# 07-General_I2C_Devices.net
KiCad netlist of a schematic drawn in Altium Designer
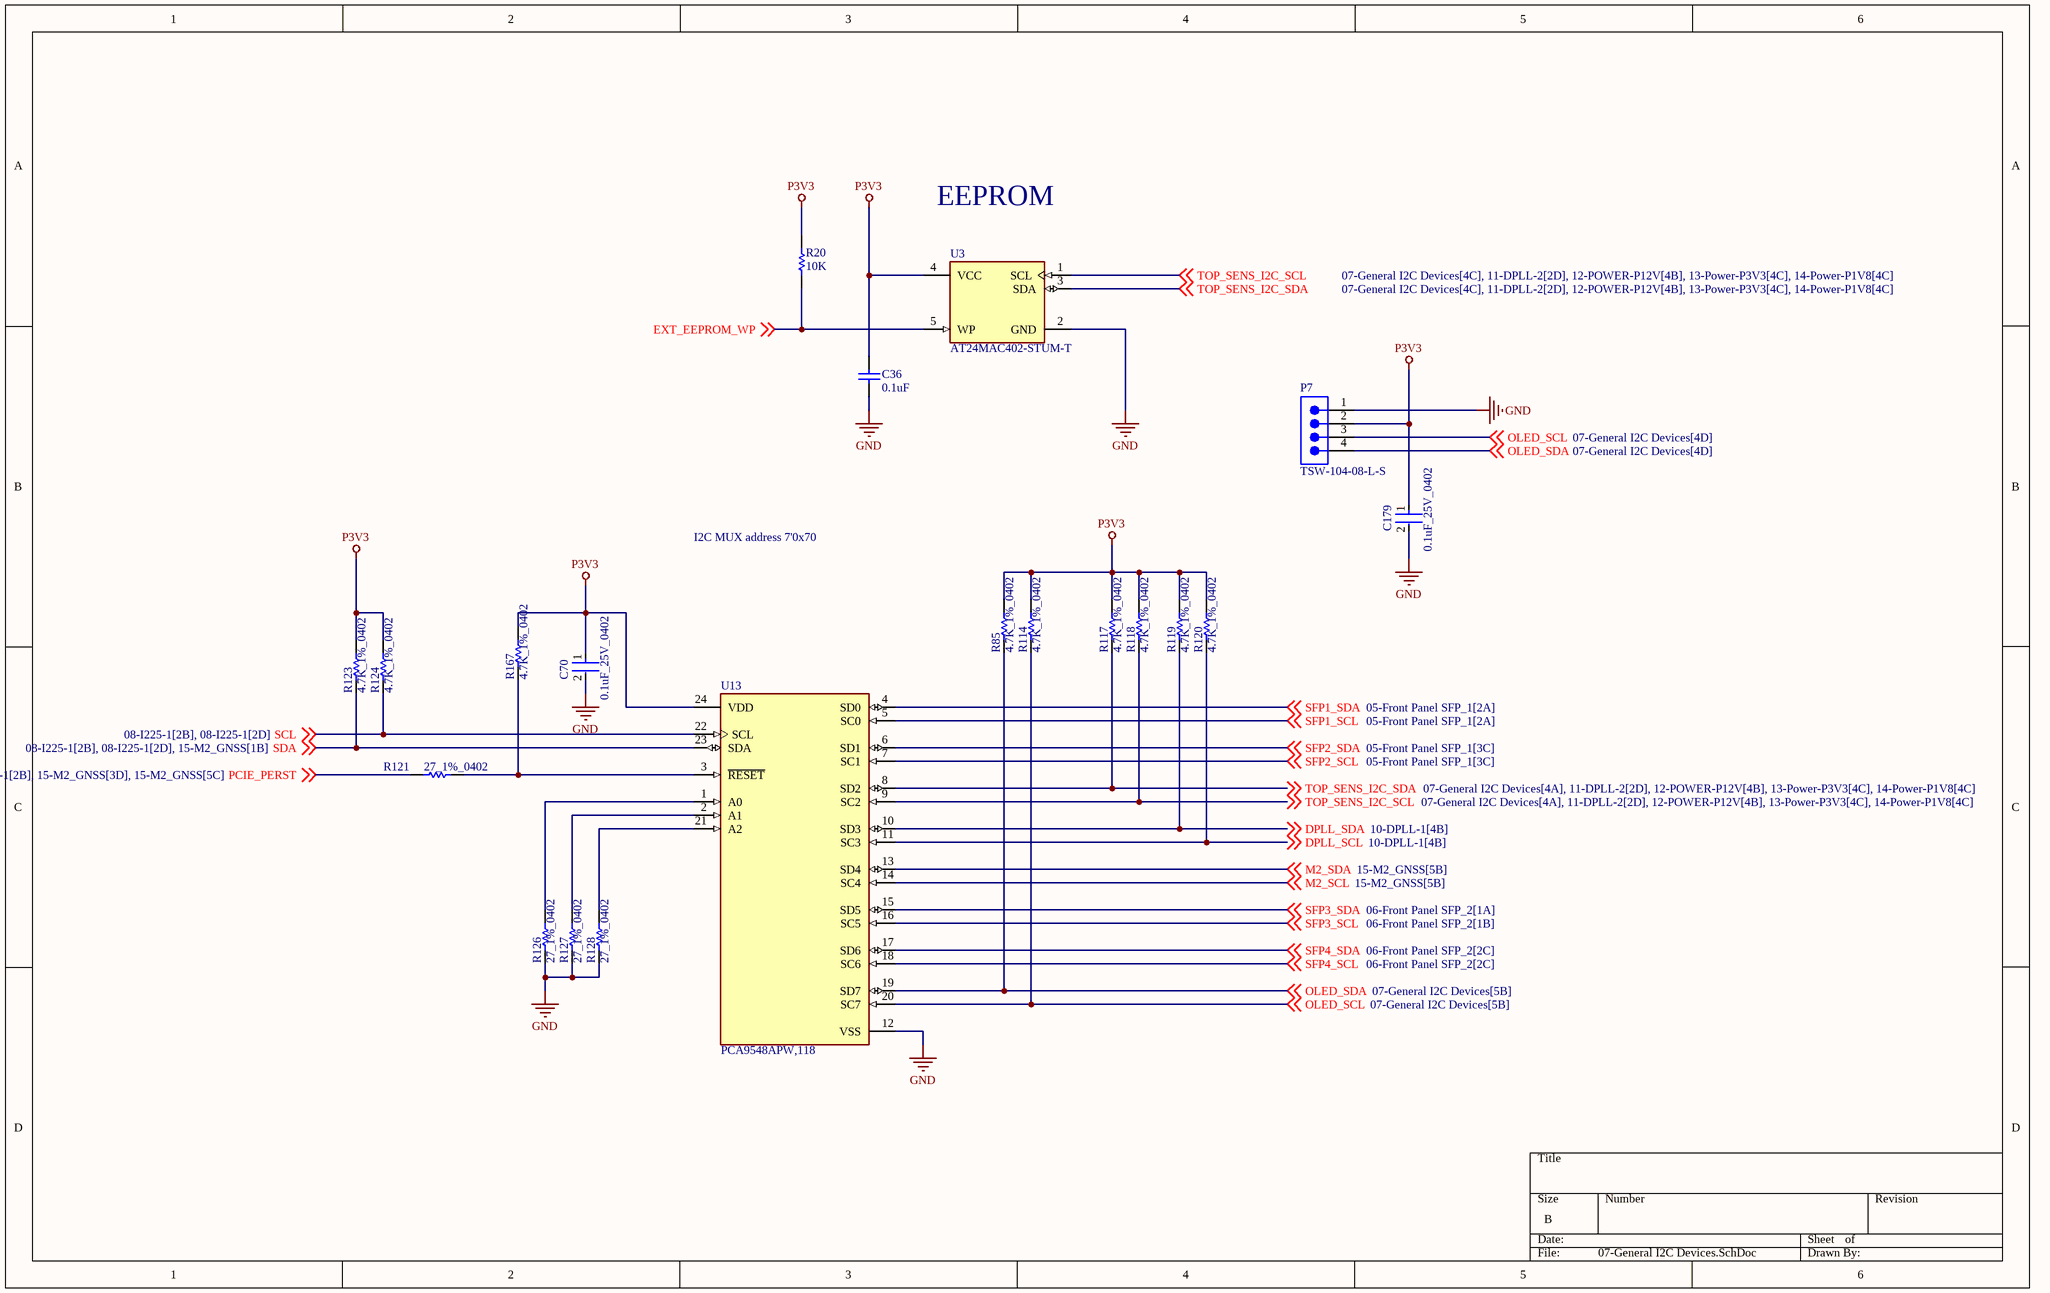
[diagram p0: 07-General I2C Devices.SchDoc]

(export (version "E")
  (design (tool "Eeschema 10.0.6"))
  (components
    (comp (ref "C36")
      (value "0.1uF")
      (footprint "CAPC1608X87X45ML20T05")
      (description "C0603X104K5RACAUTO")
      (fields (field (name "MANUFACTURER") "Kemet"))
      (libsource (lib "Altium Content Vault") (part "CAP"))
    )
    (comp (ref "C70")
      (value "0.1uF_25V_0402")
      (footprint "FP-0402-L_1_0_1-W_0_5_0_1-IPC_C")
      (description "General Purpose Ceramic Capacitor, 0402, 100nF, 10%, X7R, 15%, 25V")
      (fields (field (name "VOLTAGE") "25V") (field (name "TOLERANCE") "10%"))
      (libsource (lib "Altium Content Vault") (part "b4654b650e69147ec39a6b967a45e02"))
    )
    (comp (ref "C179")
      (value "0.1uF_25V_0402")
      (footprint "FP-0402-L_1_0_1-W_0_5_0_1-IPC_C")
      (description "General Purpose Ceramic Capacitor, 0402, 100nF, 10%, X7R, 15%, 25V")
      (fields (field (name "VOLTAGE") "25V") (field (name "TOLERANCE") "10%"))
      (libsource (lib "Altium Content Vault") (part "b4654b650e69147ec39a6b967a45e02"))
    )
    (comp (ref "P7")
      (value "TSW-104-08-L-S")
      (footprint "SMTC-TSW-104-08-X-S")
      (description "0.025\" SQ Post Header, Through-hole, Vertical, -55 to 125 degC, 2.54 mm Pitch, 4-Pin, Male, RoHS")
      (fields (field (name "MANUFACTURER") "Samtec"))
      (libsource (lib "Altium Content Vault") (part "SMTC-TSW-104-08-X-S"))
    )
    (comp (ref "R20")
      (value "10K")
      (footprint "RESC1608X55X30LL15T20")
      (fields (field (name "TOLERANCE") "±1%") (field (name "MANUFACTURER") "Stackpole-Electronics-Inc."))
      (libsource (lib "Altium Content Vault") (part "RES-2"))
    )
    (comp (ref "R85")
      (value "4.7K_1%_0402")
      (footprint "RESC1005X40X25NL10T10")
      (fields (field (name "MANUFACTURER") "Bourns") (field (name "PART NUMBER") "CR0402-FX-4701GLF"))
      (libsource (lib "Altium Content Vault") (part "RES"))
    )
    (comp (ref "R114")
      (value "4.7K_1%_0402")
      (footprint "RESC1005X40X25NL10T10")
      (fields (field (name "MANUFACTURER") "Bourns") (field (name "PART NUMBER") "CR0402-FX-4701GLF"))
      (libsource (lib "Altium Content Vault") (part "RES"))
    )
    (comp (ref "R117")
      (value "4.7K_1%_0402")
      (footprint "RESC1005X40X25NL10T10")
      (fields (field (name "MANUFACTURER") "Bourns") (field (name "PART NUMBER") "CR0402-FX-4701GLF"))
      (libsource (lib "Altium Content Vault") (part "RES"))
    )
    (comp (ref "R118")
      (value "4.7K_1%_0402")
      (footprint "RESC1005X40X25NL10T10")
      (fields (field (name "MANUFACTURER") "Bourns") (field (name "PART NUMBER") "CR0402-FX-4701GLF"))
      (libsource (lib "Altium Content Vault") (part "RES"))
    )
    (comp (ref "R119")
      (value "4.7K_1%_0402")
      (footprint "RESC1005X40X25NL10T10")
      (fields (field (name "MANUFACTURER") "Bourns") (field (name "PART NUMBER") "CR0402-FX-4701GLF"))
      (libsource (lib "Altium Content Vault") (part "RES"))
    )
    (comp (ref "R120")
      (value "4.7K_1%_0402")
      (footprint "RESC1005X40X25NL10T10")
      (fields (field (name "MANUFACTURER") "Bourns") (field (name "PART NUMBER") "CR0402-FX-4701GLF"))
      (libsource (lib "Altium Content Vault") (part "RES"))
    )
    (comp (ref "R121")
      (value "27_1%_0402")
      (footprint "RESC1005X40X25NL05T05")
      (fields (field (name "PART NUMBER") "CRCW040227R0FKED") (field (name "MANUFACTURER") "Vishay Dale"))
      (libsource (lib "Altium Content Vault") (part "RES"))
    )
    (comp (ref "R123")
      (value "4.7K_1%_0402")
      (footprint "RESC1005X40X25NL10T10")
      (fields (field (name "MANUFACTURER") "Bourns") (field (name "PART NUMBER") "CR0402-FX-4701GLF"))
      (libsource (lib "Altium Content Vault") (part "RES"))
    )
    (comp (ref "R124")
      (value "4.7K_1%_0402")
      (footprint "RESC1005X40X25NL10T10")
      (fields (field (name "MANUFACTURER") "Bourns") (field (name "PART NUMBER") "CR0402-FX-4701GLF"))
      (libsource (lib "Altium Content Vault") (part "RES"))
    )
    (comp (ref "R126")
      (value "27_1%_0402")
      (footprint "RESC1005X40X25NL05T05")
      (fields (field (name "PART NUMBER") "CRCW040227R0FKED") (field (name "MANUFACTURER") "Vishay Dale"))
      (libsource (lib "Altium Content Vault") (part "RES"))
    )
    (comp (ref "R127")
      (value "27_1%_0402")
      (footprint "RESC1005X40X25NL05T05")
      (fields (field (name "PART NUMBER") "CRCW040227R0FKED") (field (name "MANUFACTURER") "Vishay Dale"))
      (libsource (lib "Altium Content Vault") (part "RES"))
    )
    (comp (ref "R128")
      (value "27_1%_0402")
      (footprint "RESC1005X40X25NL05T05")
      (fields (field (name "PART NUMBER") "CRCW040227R0FKED") (field (name "MANUFACTURER") "Vishay Dale"))
      (libsource (lib "Altium Content Vault") (part "RES"))
    )
    (comp (ref "R167")
      (value "4.7K_1%_0402")
      (footprint "RESC1005X40X25NL10T10")
      (fields (field (name "MANUFACTURER") "Bourns") (field (name "PART NUMBER") "CR0402-FX-4701GLF"))
      (libsource (lib "Altium Content Vault") (part "RES"))
    )
    (comp (ref "U3")
      (value "AT24MAC402-STUM-T")
      (footprint "FP-5TS1-IPC_C")
      (description "IC EEPROM 2K I2C 1MHZ SOT23-5")
      (fields
        (field (name "MANUFACTURER") "Microchip")
        (field (name "OCTOPART") "https://octopart.com/at24mac402-stum-t-microchip-77758112")
      )
      (libsource (lib "Altium Content Vault") (part "93fe34f5f049140596bab6421a6454b"))
    )
    (comp (ref "U13")
      (value "PCA9548APW,118")
      (footprint "FP-SOT355-1-MFG")
      (description "IC INTERFACE SPECIALIZED 24TSSOP")
      (libsource (lib "Altium Content Vault") (part "3e168d29e2cae1e9eb34f21911d2ccb"))
    )
  )
  (nets
    (net (code "1") (name "DPLL_SCL") (class "Default")
      (node (ref "R120") (pin "1") (pinfunction "1_1") (pintype "passive"))
      (node (ref "U13") (pin "11") (pinfunction "SC3_11") (pintype "input"))
    )
    (net (code "2") (name "DPLL_SDA") (class "Default")
      (node (ref "R119") (pin "1") (pinfunction "1_1") (pintype "passive"))
      (node (ref "U13") (pin "10") (pinfunction "SD3_10") (pintype "bidirectional"))
    )
    (net (code "3") (name "EXT_EEPROM_WP") (class "Default")
      (node (ref "R20") (pin "1") (pinfunction "1_1") (pintype "passive"))
      (node (ref "U3") (pin "5") (pinfunction "WP_5") (pintype "input"))
    )
    (net (code "4") (name "GND") (class "Default")
      (node (ref "C179") (pin "2") (pinfunction "2_2") (pintype "passive"))
      (node (ref "C36") (pin "1") (pinfunction "1_1") (pintype "passive"))
      (node (ref "C70") (pin "2") (pinfunction "2_2") (pintype "passive"))
      (node (ref "P7") (pin "1") (pinfunction "1_1") (pintype "passive"))
      (node (ref "R126") (pin "1") (pinfunction "1_1") (pintype "passive"))
      (node (ref "R127") (pin "1") (pinfunction "1_1") (pintype "passive"))
      (node (ref "R128") (pin "1") (pinfunction "1_1") (pintype "passive"))
      (node (ref "U13") (pin "12") (pinfunction "VSS_12") (pintype "power_in"))
      (node (ref "U3") (pin "2") (pinfunction "GND_2") (pintype "power_in"))
    )
    (net (code "5") (name "M2_SCL") (class "Default")
      (node (ref "U13") (pin "14") (pinfunction "SC4_14") (pintype "input"))
    )
    (net (code "6") (name "M2_SDA") (class "Default")
      (node (ref "U13") (pin "13") (pinfunction "SD4_13") (pintype "bidirectional"))
    )
    (net (code "7") (name "Net-(U13-A0)") (class "Default")
      (node (ref "R126") (pin "2") (pinfunction "2_2") (pintype "passive"))
      (node (ref "U13") (pin "1") (pinfunction "A0_1") (pintype "input"))
    )
    (net (code "8") (name "Net-(U13-A1)") (class "Default")
      (node (ref "R127") (pin "2") (pinfunction "2_2") (pintype "passive"))
      (node (ref "U13") (pin "2") (pinfunction "A1_2") (pintype "input"))
    )
    (net (code "9") (name "Net-(U13-A2)") (class "Default")
      (node (ref "R128") (pin "2") (pinfunction "2_2") (pintype "passive"))
      (node (ref "U13") (pin "21") (pinfunction "A2_21") (pintype "input"))
    )
    (net (code "10") (name "Net-(U13-~{RESET})") (class "Default")
      (node (ref "R121") (pin "2") (pinfunction "2_2") (pintype "passive"))
      (node (ref "R167") (pin "1") (pinfunction "1_1") (pintype "passive"))
      (node (ref "U13") (pin "3") (pinfunction "~{RESET}_3") (pintype "input"))
    )
    (net (code "11") (name "OLED_SCL") (class "Default")
      (node (ref "P7") (pin "3") (pinfunction "3_3") (pintype "passive"))
      (node (ref "R114") (pin "1") (pinfunction "1_1") (pintype "passive"))
      (node (ref "U13") (pin "20") (pinfunction "SC7_20") (pintype "input"))
    )
    (net (code "12") (name "OLED_SDA") (class "Default")
      (node (ref "P7") (pin "4") (pinfunction "4_4") (pintype "passive"))
      (node (ref "R85") (pin "1") (pinfunction "1_1") (pintype "passive"))
      (node (ref "U13") (pin "19") (pinfunction "SD7_19") (pintype "bidirectional"))
    )
    (net (code "13") (name "P3V3") (class "Default")
      (node (ref "C179") (pin "1") (pinfunction "1_1") (pintype "passive"))
      (node (ref "C36") (pin "2") (pinfunction "2_2") (pintype "passive"))
      (node (ref "C70") (pin "1") (pinfunction "1_1") (pintype "passive"))
      (node (ref "P7") (pin "2") (pinfunction "2_2") (pintype "passive"))
      (node (ref "R114") (pin "2") (pinfunction "2_2") (pintype "passive"))
      (node (ref "R117") (pin "2") (pinfunction "2_2") (pintype "passive"))
      (node (ref "R118") (pin "2") (pinfunction "2_2") (pintype "passive"))
      (node (ref "R119") (pin "2") (pinfunction "2_2") (pintype "passive"))
      (node (ref "R120") (pin "2") (pinfunction "2_2") (pintype "passive"))
      (node (ref "R123") (pin "2") (pinfunction "2_2") (pintype "passive"))
      (node (ref "R124") (pin "2") (pinfunction "2_2") (pintype "passive"))
      (node (ref "R167") (pin "2") (pinfunction "2_2") (pintype "passive"))
      (node (ref "R20") (pin "2") (pinfunction "2_2") (pintype "passive"))
      (node (ref "R85") (pin "2") (pinfunction "2_2") (pintype "passive"))
      (node (ref "U13") (pin "24") (pinfunction "VDD_24") (pintype "power_in"))
      (node (ref "U3") (pin "4") (pinfunction "VCC_4") (pintype "power_in"))
    )
    (net (code "14") (name "PCIE_PERST") (class "Default")
      (node (ref "R121") (pin "1") (pinfunction "1_1") (pintype "passive"))
    )
    (net (code "15") (name "SCL") (class "Default")
      (node (ref "R124") (pin "1") (pinfunction "1_1") (pintype "passive"))
      (node (ref "U13") (pin "22") (pinfunction "SCL_22") (pintype "input"))
    )
    (net (code "16") (name "SDA") (class "Default")
      (node (ref "R123") (pin "1") (pinfunction "1_1") (pintype "passive"))
      (node (ref "U13") (pin "23") (pinfunction "SDA_23") (pintype "bidirectional"))
    )
    (net (code "17") (name "SFP1_SCL") (class "Default")
      (node (ref "U13") (pin "5") (pinfunction "SC0_5") (pintype "input"))
    )
    (net (code "18") (name "SFP1_SDA") (class "Default")
      (node (ref "U13") (pin "4") (pinfunction "SD0_4") (pintype "bidirectional"))
    )
    (net (code "19") (name "SFP2_SCL") (class "Default")
      (node (ref "U13") (pin "7") (pinfunction "SC1_7") (pintype "input"))
    )
    (net (code "20") (name "SFP2_SDA") (class "Default")
      (node (ref "U13") (pin "6") (pinfunction "SD1_6") (pintype "bidirectional"))
    )
    (net (code "21") (name "SFP3_SCL") (class "Default")
      (node (ref "U13") (pin "16") (pinfunction "SC5_16") (pintype "input"))
    )
    (net (code "22") (name "SFP3_SDA") (class "Default")
      (node (ref "U13") (pin "15") (pinfunction "SD5_15") (pintype "bidirectional"))
    )
    (net (code "23") (name "SFP4_SCL") (class "Default")
      (node (ref "U13") (pin "18") (pinfunction "SC6_18") (pintype "input"))
    )
    (net (code "24") (name "SFP4_SDA") (class "Default")
      (node (ref "U13") (pin "17") (pinfunction "SD6_17") (pintype "bidirectional"))
    )
    (net (code "25") (name "TOP_SENS_I2C_SCL") (class "Default")
      (node (ref "R118") (pin "1") (pinfunction "1_1") (pintype "passive"))
      (node (ref "U13") (pin "9") (pinfunction "SC2_9") (pintype "input"))
      (node (ref "U3") (pin "1") (pinfunction "SCL_1") (pintype "input"))
    )
    (net (code "26") (name "TOP_SENS_I2C_SDA") (class "Default")
      (node (ref "R117") (pin "1") (pinfunction "1_1") (pintype "passive"))
      (node (ref "U13") (pin "8") (pinfunction "SD2_8") (pintype "bidirectional"))
      (node (ref "U3") (pin "3") (pinfunction "SDA_3") (pintype "bidirectional"))
    )
  )
)
